# output_board.net
KiCad netlist of a schematic drawn in EAGLE
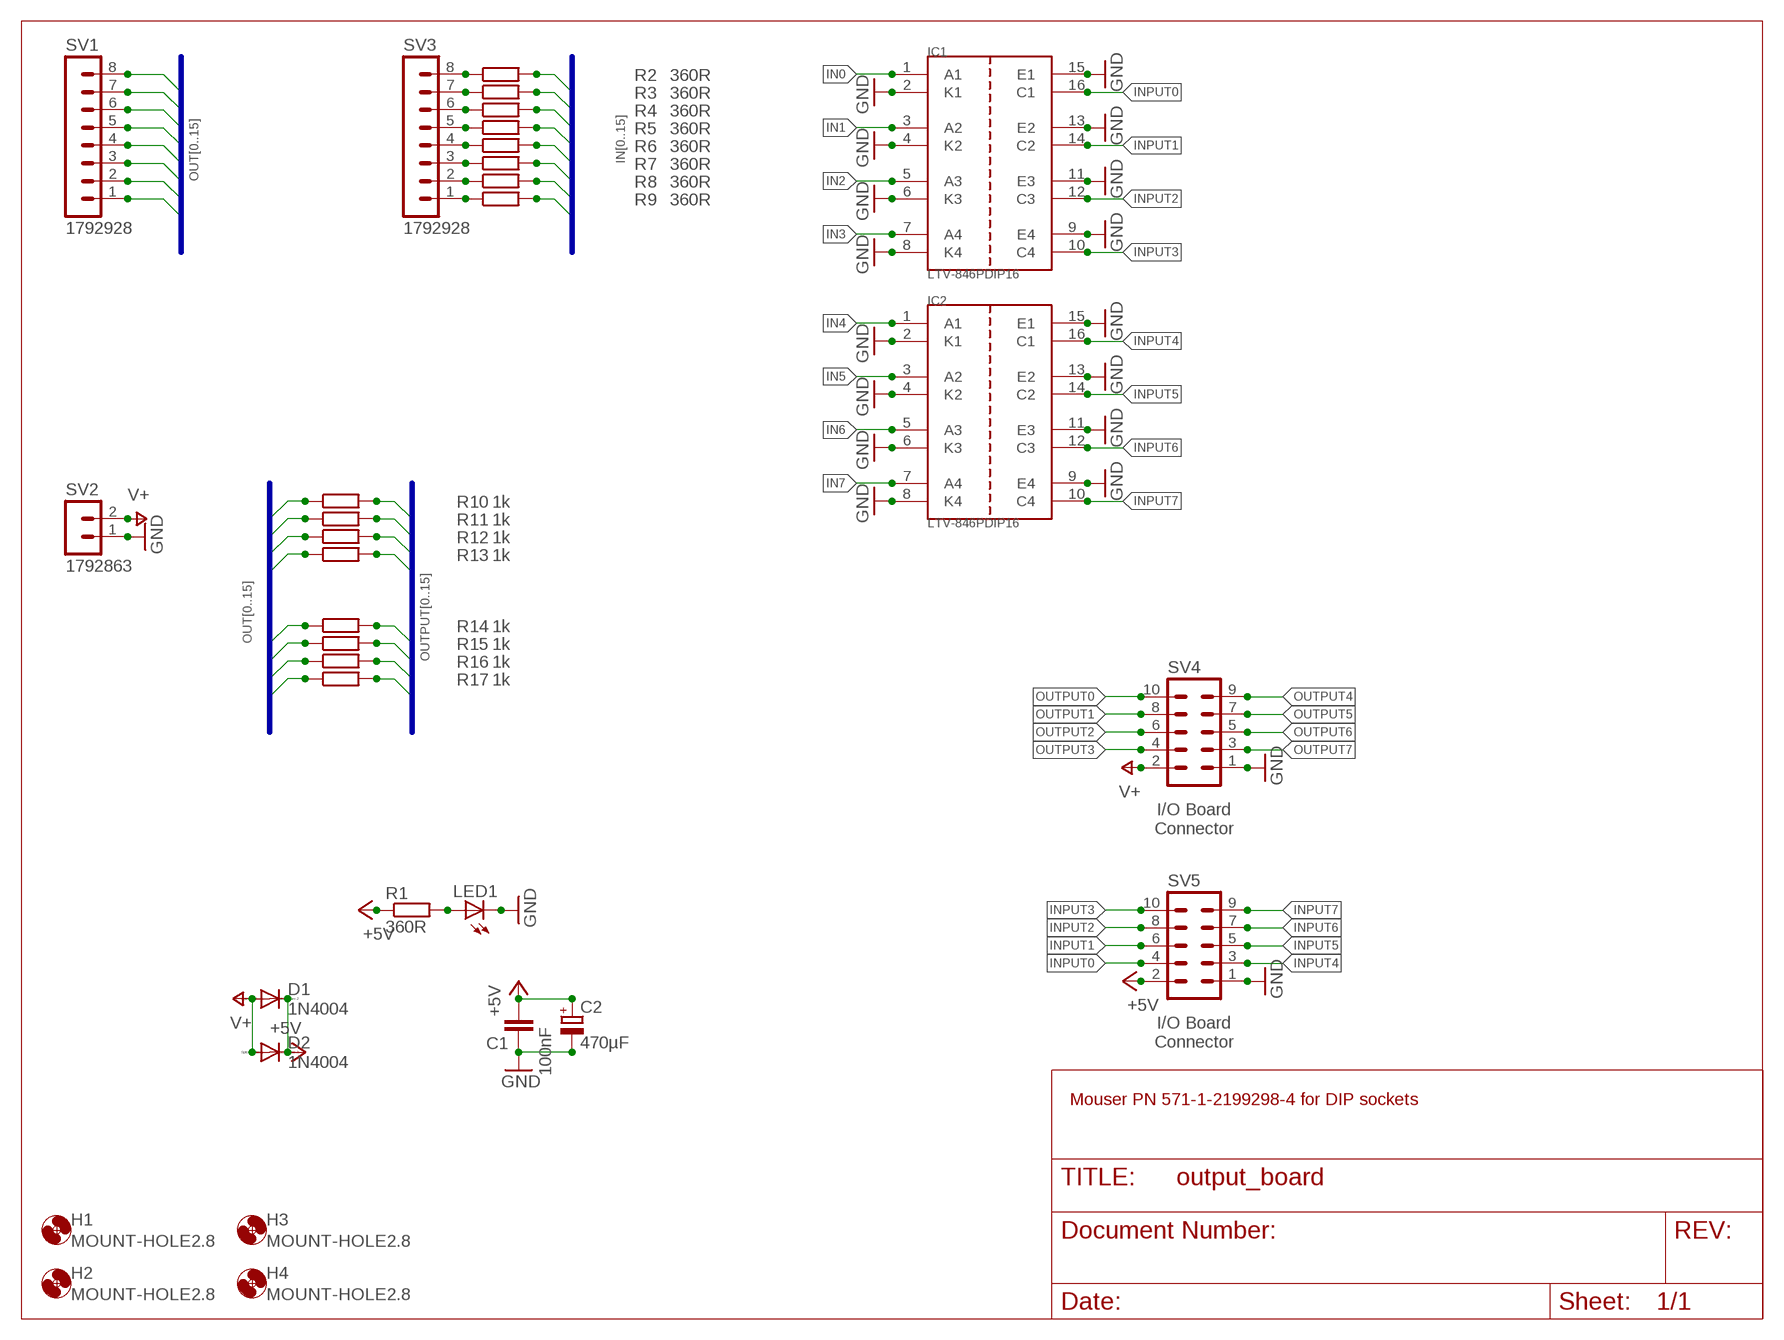
[diagram p0: schematic, sheet 1]

(export (version "E")
  (design (tool "Eeschema 10.0.6"))
  (components
    (comp (ref "C1")
      (value "100nF")
      (footprint "eagle-import:C0805")
      (libsource (lib "eagle-import") (part "C-EUC0805"))
    )
    (comp (ref "C2")
      (value "470µF")
      (footprint "eagle-import:E5-10,5")
      (libsource (lib "eagle-import") (part "CPOL-EUE5-10.5"))
    )
    (comp (ref "D1")
      (value "1N4004")
      (footprint "eagle-import:DO41-10")
      (libsource (lib "eagle-import") (part "1N4004"))
    )
    (comp (ref "D2")
      (value "1N4004")
      (footprint "eagle-import:DO41-10")
      (libsource (lib "eagle-import") (part "1N4004"))
    )
    (comp (ref "H1")
      (value "MOUNT-HOLE2.8")
      (footprint "eagle-import:2,8")
      (libsource (lib "eagle-import") (part "MOUNT-HOLE2.8"))
    )
    (comp (ref "H2")
      (value "MOUNT-HOLE2.8")
      (footprint "eagle-import:2,8")
      (libsource (lib "eagle-import") (part "MOUNT-HOLE2.8"))
    )
    (comp (ref "H3")
      (value "MOUNT-HOLE2.8")
      (footprint "eagle-import:2,8")
      (libsource (lib "eagle-import") (part "MOUNT-HOLE2.8"))
    )
    (comp (ref "H4")
      (value "MOUNT-HOLE2.8")
      (footprint "eagle-import:2,8")
      (libsource (lib "eagle-import") (part "MOUNT-HOLE2.8"))
    )
    (comp (ref "IC1")
      (value "LTV-846PDIP16")
      (footprint "eagle-import:DIL16")
      (libsource (lib "eagle-import") (part "LTV-846PDIP16"))
    )
    (comp (ref "IC2")
      (value "LTV-846PDIP16")
      (footprint "eagle-import:DIL16")
      (libsource (lib "eagle-import") (part "LTV-846PDIP16"))
    )
    (comp (ref "LED1")
      (value "LEDCHIPLED_1206")
      (footprint "eagle-import:CHIPLED_1206")
      (libsource (lib "eagle-import") (part "LEDCHIPLED_1206"))
    )
    (comp (ref "R1")
      (value "360R")
      (footprint "eagle-import:M0805")
      (libsource (lib "eagle-import") (part "R-EU_M0805"))
    )
    (comp (ref "R2")
      (value "360R")
      (footprint "eagle-import:M0805")
      (libsource (lib "eagle-import") (part "R-EU_M0805"))
    )
    (comp (ref "R3")
      (value "360R")
      (footprint "eagle-import:M0805")
      (libsource (lib "eagle-import") (part "R-EU_M0805"))
    )
    (comp (ref "R4")
      (value "360R")
      (footprint "eagle-import:M0805")
      (libsource (lib "eagle-import") (part "R-EU_M0805"))
    )
    (comp (ref "R5")
      (value "360R")
      (footprint "eagle-import:M0805")
      (libsource (lib "eagle-import") (part "R-EU_M0805"))
    )
    (comp (ref "R6")
      (value "360R")
      (footprint "eagle-import:M0805")
      (libsource (lib "eagle-import") (part "R-EU_M0805"))
    )
    (comp (ref "R7")
      (value "360R")
      (footprint "eagle-import:M0805")
      (libsource (lib "eagle-import") (part "R-EU_M0805"))
    )
    (comp (ref "R8")
      (value "360R")
      (footprint "eagle-import:M0805")
      (libsource (lib "eagle-import") (part "R-EU_M0805"))
    )
    (comp (ref "R9")
      (value "360R")
      (footprint "eagle-import:M0805")
      (libsource (lib "eagle-import") (part "R-EU_M0805"))
    )
    (comp (ref "R10")
      (value "1k")
      (footprint "eagle-import:M0805")
      (libsource (lib "eagle-import") (part "R-EU_M0805"))
    )
    (comp (ref "R11")
      (value "1k")
      (footprint "eagle-import:M0805")
      (libsource (lib "eagle-import") (part "R-EU_M0805"))
    )
    (comp (ref "R12")
      (value "1k")
      (footprint "eagle-import:M0805")
      (libsource (lib "eagle-import") (part "R-EU_M0805"))
    )
    (comp (ref "R13")
      (value "1k")
      (footprint "eagle-import:M0805")
      (libsource (lib "eagle-import") (part "R-EU_M0805"))
    )
    (comp (ref "R14")
      (value "1k")
      (footprint "eagle-import:M0805")
      (libsource (lib "eagle-import") (part "R-EU_M0805"))
    )
    (comp (ref "R15")
      (value "1k")
      (footprint "eagle-import:M0805")
      (libsource (lib "eagle-import") (part "R-EU_M0805"))
    )
    (comp (ref "R16")
      (value "1k")
      (footprint "eagle-import:M0805")
      (libsource (lib "eagle-import") (part "R-EU_M0805"))
    )
    (comp (ref "R17")
      (value "1k")
      (footprint "eagle-import:M0805")
      (libsource (lib "eagle-import") (part "R-EU_M0805"))
    )
    (comp (ref "SV1")
      (value "1792928")
      (footprint "eagle-import:1792928")
      (fields (field (name "MOUSER") "651-1792928"))
      (libsource (lib "eagle-import") (part "1792928"))
    )
    (comp (ref "SV2")
      (value "1792863")
      (footprint "eagle-import:1792863")
      (libsource (lib "eagle-import") (part "1792863"))
    )
    (comp (ref "SV3")
      (value "1792928")
      (footprint "eagle-import:1792928")
      (fields (field (name "MOUSER") "651-1792928"))
      (libsource (lib "eagle-import") (part "1792928"))
    )
    (comp (ref "SV4")
      (value "MA05-2")
      (footprint "eagle-import:MA05-2")
      (libsource (lib "eagle-import") (part "MA05-2"))
    )
    (comp (ref "SV5")
      (value "MA05-2")
      (footprint "eagle-import:MA05-2")
      (libsource (lib "eagle-import") (part "MA05-2"))
    )
  )
  (nets
    (net (code "25") (name "+5V") (class "Default")
      (node (ref "C1") (pin "2") (pinfunction "2_2") (pintype "passive"))
      (node (ref "C2") (pin "+") (pinfunction "+_+") (pintype "passive"))
      (node (ref "D1") (pin "C") (pinfunction "C_C") (pintype "passive"))
      (node (ref "D2") (pin "C") (pinfunction "C_C") (pintype "passive"))
      (node (ref "R1") (pin "1") (pinfunction "1_1") (pintype "passive"))
      (node (ref "SV5") (pin "2") (pinfunction "2_2") (pintype "passive"))
    )
    (net (code "27") (name "/OUT0") (class "Default")
      (node (ref "R10") (pin "1") (pinfunction "1_1") (pintype "passive"))
      (node (ref "SV1") (pin "1") (pinfunction "1_1") (pintype "passive"))
    )
    (net (code "28") (name "/OUT1") (class "Default")
      (node (ref "R11") (pin "1") (pinfunction "1_1") (pintype "passive"))
      (node (ref "SV1") (pin "2") (pinfunction "2_2") (pintype "passive"))
    )
    (net (code "29") (name "/OUT2") (class "Default")
      (node (ref "R12") (pin "1") (pinfunction "1_1") (pintype "passive"))
      (node (ref "SV1") (pin "3") (pinfunction "3_3") (pintype "passive"))
    )
    (net (code "30") (name "/OUT3") (class "Default")
      (node (ref "R13") (pin "1") (pinfunction "1_1") (pintype "passive"))
      (node (ref "SV1") (pin "4") (pinfunction "4_4") (pintype "passive"))
    )
    (net (code "31") (name "/OUT4") (class "Default")
      (node (ref "R14") (pin "1") (pinfunction "1_1") (pintype "passive"))
      (node (ref "SV1") (pin "5") (pinfunction "5_5") (pintype "passive"))
    )
    (net (code "32") (name "/OUT5") (class "Default")
      (node (ref "R15") (pin "1") (pinfunction "1_1") (pintype "passive"))
      (node (ref "SV1") (pin "6") (pinfunction "6_6") (pintype "passive"))
    )
    (net (code "33") (name "/OUT6") (class "Default")
      (node (ref "R16") (pin "1") (pinfunction "1_1") (pintype "passive"))
      (node (ref "SV1") (pin "7") (pinfunction "7_7") (pintype "passive"))
    )
    (net (code "34") (name "/OUT7") (class "Default")
      (node (ref "R17") (pin "1") (pinfunction "1_1") (pintype "passive"))
      (node (ref "SV1") (pin "8") (pinfunction "8_8") (pintype "passive"))
    )
    (net (code "37") (name "GND") (class "Default")
      (node (ref "C1") (pin "1") (pinfunction "1_1") (pintype "passive"))
      (node (ref "C2") (pin "-") (pinfunction "-_-") (pintype "passive"))
      (node (ref "IC1") (pin "11") (pinfunction "E3_11") (pintype "bidirectional"))
      (node (ref "IC1") (pin "13") (pinfunction "E2_13") (pintype "bidirectional"))
      (node (ref "IC1") (pin "15") (pinfunction "E1_15") (pintype "bidirectional"))
      (node (ref "IC1") (pin "2") (pinfunction "K1_2") (pintype "bidirectional"))
      (node (ref "IC1") (pin "4") (pinfunction "K2_4") (pintype "bidirectional"))
      (node (ref "IC1") (pin "6") (pinfunction "K3_6") (pintype "bidirectional"))
      (node (ref "IC1") (pin "8") (pinfunction "K4_8") (pintype "bidirectional"))
      (node (ref "IC1") (pin "9") (pinfunction "E4_9") (pintype "bidirectional"))
      (node (ref "IC2") (pin "11") (pinfunction "E3_11") (pintype "bidirectional"))
      (node (ref "IC2") (pin "13") (pinfunction "E2_13") (pintype "bidirectional"))
      (node (ref "IC2") (pin "15") (pinfunction "E1_15") (pintype "bidirectional"))
      (node (ref "IC2") (pin "2") (pinfunction "K1_2") (pintype "bidirectional"))
      (node (ref "IC2") (pin "4") (pinfunction "K2_4") (pintype "bidirectional"))
      (node (ref "IC2") (pin "6") (pinfunction "K3_6") (pintype "bidirectional"))
      (node (ref "IC2") (pin "8") (pinfunction "K4_8") (pintype "bidirectional"))
      (node (ref "IC2") (pin "9") (pinfunction "E4_9") (pintype "bidirectional"))
      (node (ref "LED1") (pin "C") (pinfunction "C_C") (pintype "passive"))
      (node (ref "SV2") (pin "1") (pinfunction "1_1") (pintype "passive"))
      (node (ref "SV4") (pin "1") (pinfunction "1_1") (pintype "passive"))
      (node (ref "SV5") (pin "1") (pinfunction "1_1") (pintype "passive"))
    )
    (net (code "38") (name "IN0") (class "Default")
      (node (ref "IC1") (pin "1") (pinfunction "A1_1") (pintype "bidirectional"))
      (node (ref "R9") (pin "2") (pinfunction "2_2") (pintype "passive"))
    )
    (net (code "39") (name "IN1") (class "Default")
      (node (ref "IC1") (pin "3") (pinfunction "A2_3") (pintype "bidirectional"))
      (node (ref "R8") (pin "2") (pinfunction "2_2") (pintype "passive"))
    )
    (net (code "40") (name "IN2") (class "Default")
      (node (ref "IC1") (pin "5") (pinfunction "A3_5") (pintype "bidirectional"))
      (node (ref "R7") (pin "2") (pinfunction "2_2") (pintype "passive"))
    )
    (net (code "41") (name "IN3") (class "Default")
      (node (ref "IC1") (pin "7") (pinfunction "A4_7") (pintype "bidirectional"))
      (node (ref "R6") (pin "2") (pinfunction "2_2") (pintype "passive"))
    )
    (net (code "42") (name "IN4") (class "Default")
      (node (ref "IC2") (pin "1") (pinfunction "A1_1") (pintype "bidirectional"))
      (node (ref "R5") (pin "2") (pinfunction "2_2") (pintype "passive"))
    )
    (net (code "43") (name "IN5") (class "Default")
      (node (ref "IC2") (pin "3") (pinfunction "A2_3") (pintype "bidirectional"))
      (node (ref "R4") (pin "2") (pinfunction "2_2") (pintype "passive"))
    )
    (net (code "44") (name "IN6") (class "Default")
      (node (ref "IC2") (pin "5") (pinfunction "A3_5") (pintype "bidirectional"))
      (node (ref "R3") (pin "2") (pinfunction "2_2") (pintype "passive"))
    )
    (net (code "45") (name "IN7") (class "Default")
      (node (ref "IC2") (pin "7") (pinfunction "A4_7") (pintype "bidirectional"))
      (node (ref "R2") (pin "2") (pinfunction "2_2") (pintype "passive"))
    )
    (net (code "46") (name "INPUT0") (class "Default")
      (node (ref "IC1") (pin "16") (pinfunction "C1_16") (pintype "bidirectional"))
      (node (ref "SV5") (pin "4") (pinfunction "4_4") (pintype "passive"))
    )
    (net (code "47") (name "INPUT1") (class "Default")
      (node (ref "IC1") (pin "14") (pinfunction "C2_14") (pintype "bidirectional"))
      (node (ref "SV5") (pin "6") (pinfunction "6_6") (pintype "passive"))
    )
    (net (code "48") (name "INPUT2") (class "Default")
      (node (ref "IC1") (pin "12") (pinfunction "C3_12") (pintype "bidirectional"))
      (node (ref "SV5") (pin "8") (pinfunction "8_8") (pintype "passive"))
    )
    (net (code "49") (name "INPUT3") (class "Default")
      (node (ref "IC1") (pin "10") (pinfunction "C4_10") (pintype "bidirectional"))
      (node (ref "SV5") (pin "10") (pinfunction "10_10") (pintype "passive"))
    )
    (net (code "50") (name "INPUT4") (class "Default")
      (node (ref "IC2") (pin "16") (pinfunction "C1_16") (pintype "bidirectional"))
      (node (ref "SV5") (pin "3") (pinfunction "3_3") (pintype "passive"))
    )
    (net (code "51") (name "INPUT5") (class "Default")
      (node (ref "IC2") (pin "14") (pinfunction "C2_14") (pintype "bidirectional"))
      (node (ref "SV5") (pin "5") (pinfunction "5_5") (pintype "passive"))
    )
    (net (code "52") (name "INPUT6") (class "Default")
      (node (ref "IC2") (pin "12") (pinfunction "C3_12") (pintype "bidirectional"))
      (node (ref "SV5") (pin "7") (pinfunction "7_7") (pintype "passive"))
    )
    (net (code "53") (name "INPUT7") (class "Default")
      (node (ref "IC2") (pin "10") (pinfunction "C4_10") (pintype "bidirectional"))
      (node (ref "SV5") (pin "9") (pinfunction "9_9") (pintype "passive"))
    )
    (net (code "54") (name "Net-(LED1-PadA)") (class "Default")
      (node (ref "LED1") (pin "A") (pinfunction "A_A") (pintype "passive"))
      (node (ref "R1") (pin "2") (pinfunction "2_2") (pintype "passive"))
    )
    (net (code "55") (name "Net-(R2-Pad1)") (class "Default")
      (node (ref "R2") (pin "1") (pinfunction "1_1") (pintype "passive"))
      (node (ref "SV3") (pin "8") (pinfunction "8_8") (pintype "passive"))
    )
    (net (code "56") (name "Net-(R3-Pad1)") (class "Default")
      (node (ref "R3") (pin "1") (pinfunction "1_1") (pintype "passive"))
      (node (ref "SV3") (pin "7") (pinfunction "7_7") (pintype "passive"))
    )
    (net (code "57") (name "Net-(R4-Pad1)") (class "Default")
      (node (ref "R4") (pin "1") (pinfunction "1_1") (pintype "passive"))
      (node (ref "SV3") (pin "6") (pinfunction "6_6") (pintype "passive"))
    )
    (net (code "58") (name "Net-(R5-Pad1)") (class "Default")
      (node (ref "R5") (pin "1") (pinfunction "1_1") (pintype "passive"))
      (node (ref "SV3") (pin "5") (pinfunction "5_5") (pintype "passive"))
    )
    (net (code "59") (name "Net-(R6-Pad1)") (class "Default")
      (node (ref "R6") (pin "1") (pinfunction "1_1") (pintype "passive"))
      (node (ref "SV3") (pin "4") (pinfunction "4_4") (pintype "passive"))
    )
    (net (code "60") (name "Net-(R7-Pad1)") (class "Default")
      (node (ref "R7") (pin "1") (pinfunction "1_1") (pintype "passive"))
      (node (ref "SV3") (pin "3") (pinfunction "3_3") (pintype "passive"))
    )
    (net (code "61") (name "Net-(R8-Pad1)") (class "Default")
      (node (ref "R8") (pin "1") (pinfunction "1_1") (pintype "passive"))
      (node (ref "SV3") (pin "2") (pinfunction "2_2") (pintype "passive"))
    )
    (net (code "62") (name "Net-(R9-Pad1)") (class "Default")
      (node (ref "R9") (pin "1") (pinfunction "1_1") (pintype "passive"))
      (node (ref "SV3") (pin "1") (pinfunction "1_1") (pintype "passive"))
    )
    (net (code "63") (name "OUTPUT0") (class "Default")
      (node (ref "R10") (pin "2") (pinfunction "2_2") (pintype "passive"))
      (node (ref "SV4") (pin "10") (pinfunction "10_10") (pintype "passive"))
    )
    (net (code "64") (name "OUTPUT1") (class "Default")
      (node (ref "R11") (pin "2") (pinfunction "2_2") (pintype "passive"))
      (node (ref "SV4") (pin "8") (pinfunction "8_8") (pintype "passive"))
    )
    (net (code "65") (name "OUTPUT2") (class "Default")
      (node (ref "R12") (pin "2") (pinfunction "2_2") (pintype "passive"))
      (node (ref "SV4") (pin "6") (pinfunction "6_6") (pintype "passive"))
    )
    (net (code "66") (name "OUTPUT3") (class "Default")
      (node (ref "R13") (pin "2") (pinfunction "2_2") (pintype "passive"))
      (node (ref "SV4") (pin "4") (pinfunction "4_4") (pintype "passive"))
    )
    (net (code "67") (name "OUTPUT4") (class "Default")
      (node (ref "R14") (pin "2") (pinfunction "2_2") (pintype "passive"))
      (node (ref "SV4") (pin "9") (pinfunction "9_9") (pintype "passive"))
    )
    (net (code "68") (name "OUTPUT5") (class "Default")
      (node (ref "R15") (pin "2") (pinfunction "2_2") (pintype "passive"))
      (node (ref "SV4") (pin "7") (pinfunction "7_7") (pintype "passive"))
    )
    (net (code "69") (name "OUTPUT6") (class "Default")
      (node (ref "R16") (pin "2") (pinfunction "2_2") (pintype "passive"))
      (node (ref "SV4") (pin "5") (pinfunction "5_5") (pintype "passive"))
    )
    (net (code "70") (name "OUTPUT7") (class "Default")
      (node (ref "R17") (pin "2") (pinfunction "2_2") (pintype "passive"))
      (node (ref "SV4") (pin "3") (pinfunction "3_3") (pintype "passive"))
    )
    (net (code "71") (name "V+") (class "Default")
      (node (ref "D1") (pin "A") (pinfunction "A_A") (pintype "passive"))
      (node (ref "D2") (pin "A") (pinfunction "A_A") (pintype "passive"))
      (node (ref "SV2") (pin "2") (pinfunction "2_2") (pintype "passive"))
      (node (ref "SV4") (pin "2") (pinfunction "2_2") (pintype "passive"))
    )
  )
)
